# vcf-v1.net
KiCad netlist of a schematic drawn in EAGLE
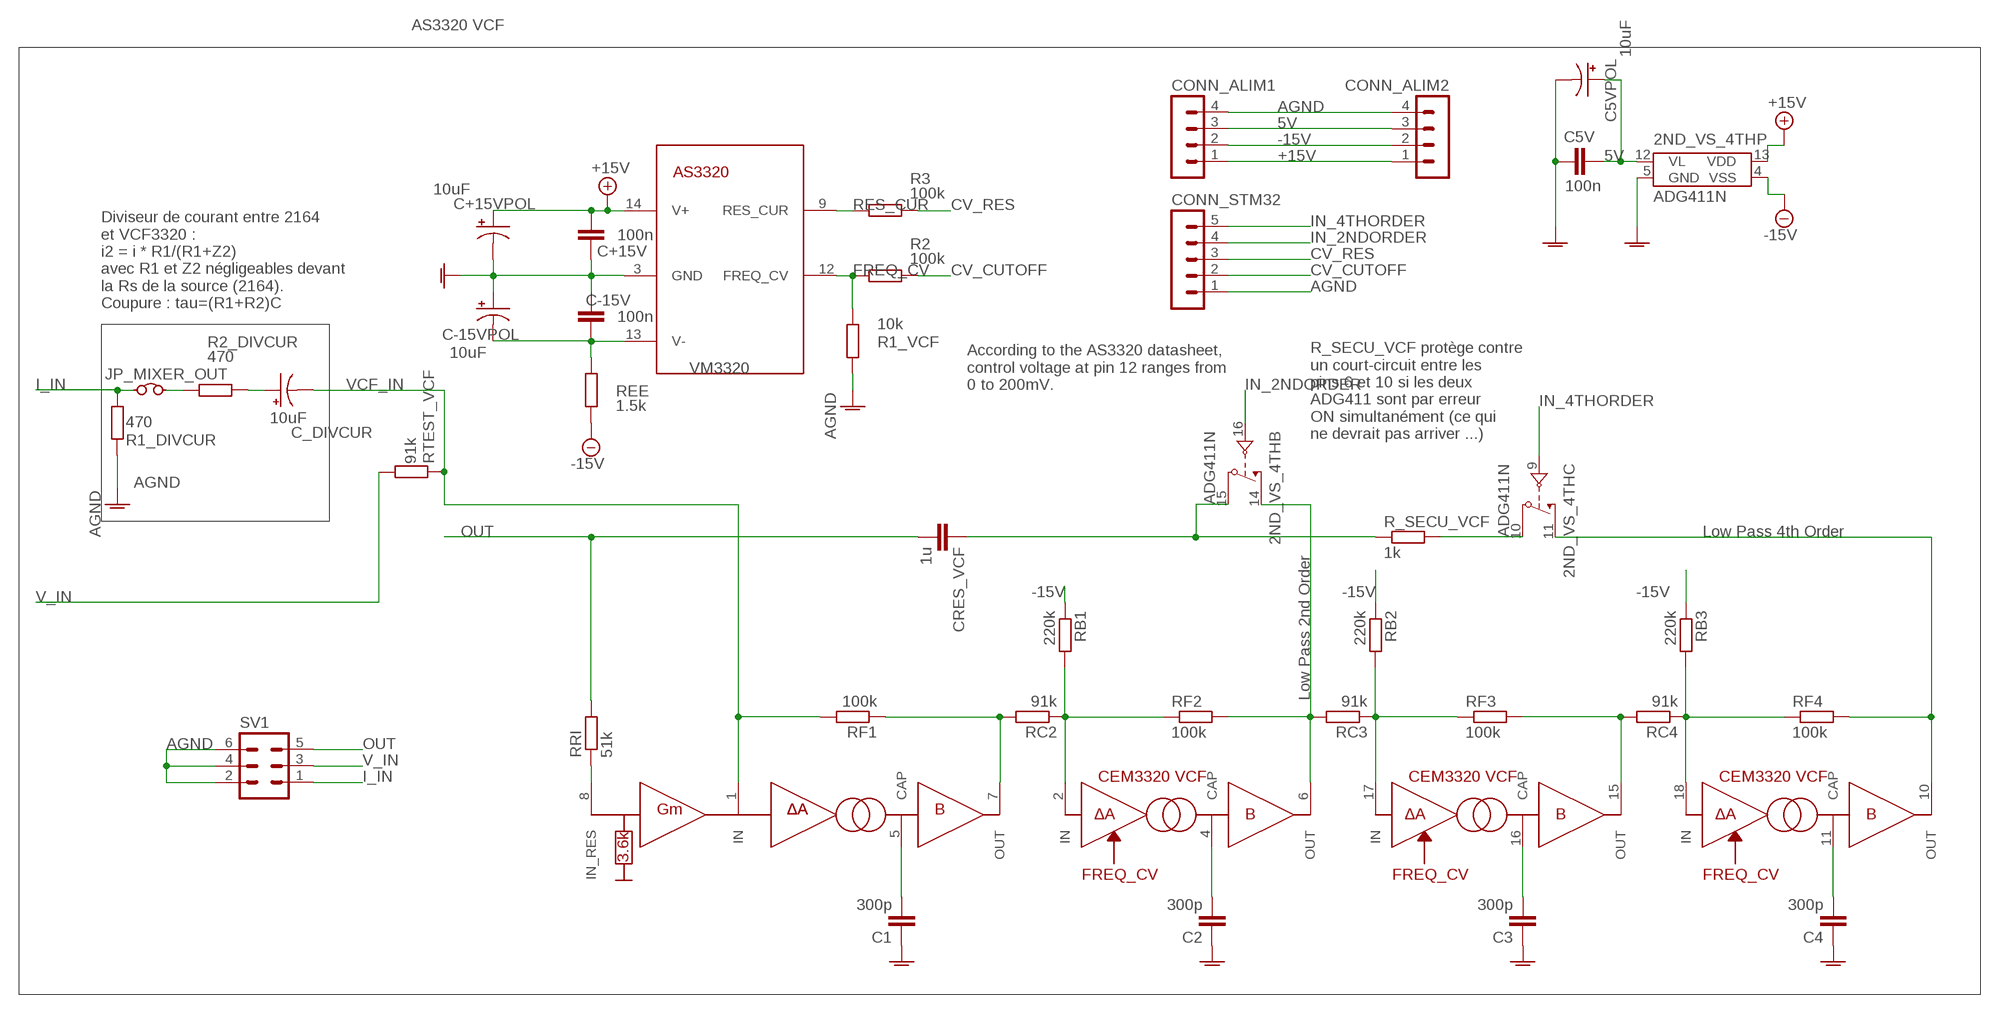
[diagram p0: schematic, sheet 1]

(export (version "E")
  (design (tool "Eeschema 10.0.6"))
  (components
    (comp (ref "2ND_VS_4TH")
      (value "ADG411N")
      (footprint "eagle-import:DIL16")
      (fields (field (name "MF") "ALTERA CORPORATION") (field (name "MPN") "ADG411BN"))
      (libsource (lib "eagle-import") (part "ADG411N"))
    )
    (comp (ref "C+15V")
      (value "100n")
      (footprint "eagle-import:C050-024X044")
      (libsource (lib "eagle-import") (part "C-EU050-024X044"))
    )
    (comp (ref "C+15VPOL")
      (value "10uF")
      (footprint "eagle-import:CPOL-RADIAL-2.5MM-5MM-KIT")
      (libsource (lib "eagle-import") (part "10UF-POLAR-RADIAL-2.5MM-KIT-25V-20%"))
    )
    (comp (ref "C-15V")
      (value "100n")
      (footprint "eagle-import:C050-024X044")
      (libsource (lib "eagle-import") (part "C-EU050-024X044"))
    )
    (comp (ref "C-15VPOL")
      (value "10uF")
      (footprint "eagle-import:CPOL-RADIAL-2.5MM-5MM-KIT")
      (libsource (lib "eagle-import") (part "10UF-POLAR-RADIAL-2.5MM-KIT-25V-20%"))
    )
    (comp (ref "C1")
      (value "300p")
      (footprint "eagle-import:C050-024X044")
      (libsource (lib "eagle-import") (part "C-EU050-024X044"))
    )
    (comp (ref "C2")
      (value "300p")
      (footprint "eagle-import:C050-024X044")
      (libsource (lib "eagle-import") (part "C-EU050-024X044"))
    )
    (comp (ref "C3")
      (value "300p")
      (footprint "eagle-import:C075-032X103")
      (libsource (lib "eagle-import") (part "C-EU075-032X103"))
    )
    (comp (ref "C4")
      (value "300p")
      (footprint "eagle-import:C050-024X044")
      (libsource (lib "eagle-import") (part "C-EU050-024X044"))
    )
    (comp (ref "C5V")
      (value "100n")
      (footprint "eagle-import:C050-024X044")
      (libsource (lib "eagle-import") (part "C-EU050-024X044"))
    )
    (comp (ref "C5VPOL")
      (value "10uF")
      (footprint "eagle-import:CPOL-RADIAL-2.5MM-5MM-KIT")
      (libsource (lib "eagle-import") (part "10UF-POLAR-RADIAL-2.5MM-KIT-25V-20%"))
    )
    (comp (ref "CONN_ALIM1")
      (value "MA04-1")
      (footprint "eagle-import:MA04-1")
      (libsource (lib "eagle-import") (part "MA04-1"))
    )
    (comp (ref "CONN_ALIM2")
      (value "MA04-1")
      (footprint "eagle-import:MA04-1")
      (libsource (lib "eagle-import") (part "MA04-1"))
    )
    (comp (ref "CONN_STM32")
      (value "MA05-1")
      (footprint "eagle-import:MA05-1")
      (libsource (lib "eagle-import") (part "MA05-1"))
    )
    (comp (ref "CRES_VCF")
      (value "1u")
      (footprint "eagle-import:C050-024X044")
      (libsource (lib "eagle-import") (part "C-EU050-024X044"))
    )
    (comp (ref "C_DIVCUR")
      (value "10uF")
      (footprint "eagle-import:CPOL-RADIAL-2.5MM-5MM-KIT")
      (libsource (lib "eagle-import") (part "10UF-POLAR-RADIAL-2.5MM-KIT-25V-20%"))
    )
    (comp (ref "JP_MIXER_OUT")
      (value "JUMPER_WIRE")
      (footprint "eagle-import:JUMPER")
      (libsource (lib "eagle-import") (part "JUMPER_WIRE"))
    )
    (comp (ref "R1_DIVCUR")
      (value "470")
      (footprint "eagle-import:0204_5")
      (libsource (lib "eagle-import") (part "R-EU_0204/5"))
    )
    (comp (ref "R1_VCF")
      (value "10k")
      (footprint "eagle-import:0204_5")
      (libsource (lib "eagle-import") (part "R-EU_0204/5"))
    )
    (comp (ref "R2")
      (value "100k")
      (footprint "eagle-import:0204_5")
      (libsource (lib "eagle-import") (part "R-EU_0204/5"))
    )
    (comp (ref "R2_DIVCUR")
      (value "470")
      (footprint "eagle-import:0204_5")
      (libsource (lib "eagle-import") (part "R-EU_0204/5"))
    )
    (comp (ref "R3")
      (value "100k")
      (footprint "eagle-import:0204_5")
      (libsource (lib "eagle-import") (part "R-EU_0204/5"))
    )
    (comp (ref "RB1")
      (value "220k")
      (footprint "eagle-import:0204_5")
      (libsource (lib "eagle-import") (part "R-EU_0204/5"))
    )
    (comp (ref "RB2")
      (value "220k")
      (footprint "eagle-import:0204_5")
      (libsource (lib "eagle-import") (part "R-EU_0204/5"))
    )
    (comp (ref "RB3")
      (value "220k")
      (footprint "eagle-import:0204_5")
      (libsource (lib "eagle-import") (part "R-EU_0204/5"))
    )
    (comp (ref "RC2")
      (value "91k")
      (footprint "eagle-import:0204_5")
      (libsource (lib "eagle-import") (part "R-EU_0204/5"))
    )
    (comp (ref "RC3")
      (value "91k")
      (footprint "eagle-import:0204_5")
      (libsource (lib "eagle-import") (part "R-EU_0204/5"))
    )
    (comp (ref "RC4")
      (value "91k")
      (footprint "eagle-import:0204_5")
      (libsource (lib "eagle-import") (part "R-EU_0204/5"))
    )
    (comp (ref "REE")
      (value "1.5k")
      (footprint "eagle-import:0204_5")
      (libsource (lib "eagle-import") (part "R-EU_0204/5"))
    )
    (comp (ref "RF1")
      (value "100k")
      (footprint "eagle-import:0204_5")
      (libsource (lib "eagle-import") (part "R-EU_0204/5"))
    )
    (comp (ref "RF2")
      (value "100k")
      (footprint "eagle-import:0204_5")
      (libsource (lib "eagle-import") (part "R-EU_0204/5"))
    )
    (comp (ref "RF3")
      (value "100k")
      (footprint "eagle-import:0204_5")
      (libsource (lib "eagle-import") (part "R-EU_0204/5"))
    )
    (comp (ref "RF4")
      (value "100k")
      (footprint "eagle-import:0204_5")
      (libsource (lib "eagle-import") (part "R-EU_0204/5"))
    )
    (comp (ref "RRI")
      (value "51k")
      (footprint "eagle-import:0204_5")
      (libsource (lib "eagle-import") (part "R-EU_0204/5"))
    )
    (comp (ref "RTEST_VCF")
      (value "91k")
      (footprint "eagle-import:0204_5")
      (libsource (lib "eagle-import") (part "R-EU_0204/5"))
    )
    (comp (ref "R_SECU_VCF")
      (value "1k")
      (footprint "eagle-import:0204_5")
      (libsource (lib "eagle-import") (part "R-EU_0204/5"))
    )
    (comp (ref "SV1")
      (value "MA03-2")
      (footprint "eagle-import:MA03-2")
      (libsource (lib "eagle-import") (part "MA03-2"))
    )
    (comp (ref "VCF")
      (value "AS3320")
      (footprint "eagle-import:DIL18")
      (libsource (lib "eagle-import") (part "AS3320"))
    )
  )
  (nets
    (net (code "1") (name "+15V") (class "Default")
      (node (ref "2ND_VS_4TH") (pin "13") (pinfunction "VDD_13") (pintype "power_in"))
      (node (ref "C+15V") (pin "2") (pinfunction "2_2") (pintype "passive"))
      (node (ref "C+15VPOL") (pin "1") (pinfunction "+_1") (pintype "passive"))
      (node (ref "CONN_ALIM1") (pin "1") (pinfunction "1_1") (pintype "passive"))
      (node (ref "CONN_ALIM2") (pin "1") (pinfunction "1_1") (pintype "passive"))
      (node (ref "VCF") (pin "14") (pinfunction "V+_14") (pintype "bidirectional"))
    )
    (net (code "2") (name "-15V") (class "Default")
      (node (ref "2ND_VS_4TH") (pin "4") (pinfunction "VSS_4") (pintype "power_in"))
      (node (ref "CONN_ALIM1") (pin "2") (pinfunction "2_2") (pintype "passive"))
      (node (ref "CONN_ALIM2") (pin "2") (pinfunction "2_2") (pintype "passive"))
      (node (ref "RB1") (pin "1") (pinfunction "1_1") (pintype "passive"))
      (node (ref "RB2") (pin "1") (pinfunction "1_1") (pintype "passive"))
      (node (ref "RB3") (pin "1") (pinfunction "1_1") (pintype "passive"))
      (node (ref "REE") (pin "1") (pinfunction "1_1") (pintype "passive"))
    )
    (net (code "3") (name "/5V") (class "Default")
      (node (ref "2ND_VS_4TH") (pin "12") (pinfunction "VL_12") (pintype "power_in"))
      (node (ref "C5V") (pin "1") (pinfunction "1_1") (pintype "passive"))
      (node (ref "C5VPOL") (pin "1") (pinfunction "+_1") (pintype "passive"))
      (node (ref "CONN_ALIM1") (pin "3") (pinfunction "3_3") (pintype "passive"))
      (node (ref "CONN_ALIM2") (pin "3") (pinfunction "3_3") (pintype "passive"))
    )
    (net (code "4") (name "/CV_CUTOFF") (class "Default")
      (node (ref "CONN_STM32") (pin "2") (pinfunction "2_2") (pintype "passive"))
      (node (ref "R2") (pin "2") (pinfunction "2_2") (pintype "passive"))
    )
    (net (code "5") (name "/CV_RES") (class "Default")
      (node (ref "CONN_STM32") (pin "3") (pinfunction "3_3") (pintype "passive"))
      (node (ref "R3") (pin "2") (pinfunction "2_2") (pintype "passive"))
    )
    (net (code "6") (name "/FREQ_CV") (class "Default")
      (node (ref "R1_VCF") (pin "1") (pinfunction "1_1") (pintype "passive"))
      (node (ref "R2") (pin "1") (pinfunction "1_1") (pintype "passive"))
      (node (ref "VCF") (pin "12") (pinfunction "FREQ_CV_12") (pintype "bidirectional"))
    )
    (net (code "7") (name "/IN_2NDORDER") (class "Default")
      (node (ref "2ND_VS_4TH") (pin "16") (pinfunction "IN_16") (pintype "input"))
      (node (ref "CONN_STM32") (pin "4") (pinfunction "4_4") (pintype "passive"))
    )
    (net (code "8") (name "/IN_4THORDER") (class "Default")
      (node (ref "2ND_VS_4TH") (pin "9") (pinfunction "IN_9") (pintype "input"))
      (node (ref "CONN_STM32") (pin "5") (pinfunction "5_5") (pintype "passive"))
    )
    (net (code "9") (name "/I_IN") (class "Default")
      (node (ref "JP_MIXER_OUT") (pin "1") (pinfunction "1_1") (pintype "passive"))
      (node (ref "R1_DIVCUR") (pin "1") (pinfunction "1_1") (pintype "passive"))
      (node (ref "SV1") (pin "1") (pinfunction "1_1") (pintype "passive"))
    )
    (net (code "10") (name "/OUT") (class "Default")
      (node (ref "CRES_VCF") (pin "2") (pinfunction "2_2") (pintype "passive"))
      (node (ref "RRI") (pin "2") (pinfunction "2_2") (pintype "passive"))
      (node (ref "SV1") (pin "5") (pinfunction "5_5") (pintype "passive"))
    )
    (net (code "11") (name "/RES_CUR") (class "Default")
      (node (ref "R3") (pin "1") (pinfunction "1_1") (pintype "passive"))
      (node (ref "VCF") (pin "9") (pinfunction "RES_CUR_9") (pintype "bidirectional"))
    )
    (net (code "12") (name "/VCF_IN") (class "Default")
      (node (ref "C_DIVCUR") (pin "2") (pinfunction "-_2") (pintype "passive"))
      (node (ref "RF1") (pin "2") (pinfunction "2_2") (pintype "passive"))
      (node (ref "RTEST_VCF") (pin "2") (pinfunction "2_2") (pintype "passive"))
      (node (ref "VCF") (pin "1") (pinfunction "IN_1") (pintype "bidirectional"))
    )
    (net (code "13") (name "/VM3320") (class "Default")
      (node (ref "C-15V") (pin "1") (pinfunction "1_1") (pintype "passive"))
      (node (ref "C-15VPOL") (pin "2") (pinfunction "-_2") (pintype "passive"))
      (node (ref "REE") (pin "2") (pinfunction "2_2") (pintype "passive"))
      (node (ref "VCF") (pin "13") (pinfunction "V-_13") (pintype "bidirectional"))
    )
    (net (code "14") (name "/V_IN") (class "Default")
      (node (ref "RTEST_VCF") (pin "1") (pinfunction "1_1") (pintype "passive"))
      (node (ref "SV1") (pin "3") (pinfunction "3_3") (pintype "passive"))
    )
    (net (code "15") (name "AGND") (class "Default")
      (node (ref "2ND_VS_4TH") (pin "5") (pinfunction "GND_5") (pintype "power_in"))
      (node (ref "C+15V") (pin "1") (pinfunction "1_1") (pintype "passive"))
      (node (ref "C+15VPOL") (pin "2") (pinfunction "-_2") (pintype "passive"))
      (node (ref "C-15V") (pin "2") (pinfunction "2_2") (pintype "passive"))
      (node (ref "C-15VPOL") (pin "1") (pinfunction "+_1") (pintype "passive"))
      (node (ref "C1") (pin "1") (pinfunction "1_1") (pintype "passive"))
      (node (ref "C2") (pin "1") (pinfunction "1_1") (pintype "passive"))
      (node (ref "C3") (pin "1") (pinfunction "1_1") (pintype "passive"))
      (node (ref "C4") (pin "1") (pinfunction "1_1") (pintype "passive"))
      (node (ref "C5V") (pin "2") (pinfunction "2_2") (pintype "passive"))
      (node (ref "C5VPOL") (pin "2") (pinfunction "-_2") (pintype "passive"))
      (node (ref "CONN_ALIM1") (pin "4") (pinfunction "4_4") (pintype "passive"))
      (node (ref "CONN_ALIM2") (pin "4") (pinfunction "4_4") (pintype "passive"))
      (node (ref "CONN_STM32") (pin "1") (pinfunction "1_1") (pintype "passive"))
      (node (ref "R1_DIVCUR") (pin "2") (pinfunction "2_2") (pintype "passive"))
      (node (ref "R1_VCF") (pin "2") (pinfunction "2_2") (pintype "passive"))
      (node (ref "SV1") (pin "2") (pinfunction "2_2") (pintype "passive"))
      (node (ref "SV1") (pin "4") (pinfunction "4_4") (pintype "passive"))
      (node (ref "SV1") (pin "6") (pinfunction "6_6") (pintype "passive"))
      (node (ref "VCF") (pin "3") (pinfunction "GND_3") (pintype "bidirectional"))
    )
    (net (code "16") (name "Net-(2ND_VS_4THB-D)") (class "Default")
      (node (ref "2ND_VS_4TH") (pin "15") (pinfunction "D_15") (pintype "passive"))
      (node (ref "CRES_VCF") (pin "1") (pinfunction "1_1") (pintype "passive"))
      (node (ref "R_SECU_VCF") (pin "1") (pinfunction "1_1") (pintype "passive"))
    )
    (net (code "17") (name "Net-(2ND_VS_4THB-S)") (class "Default")
      (node (ref "2ND_VS_4TH") (pin "14") (pinfunction "S_14") (pintype "passive"))
      (node (ref "RC3") (pin "2") (pinfunction "2_2") (pintype "passive"))
      (node (ref "RF2") (pin "2") (pinfunction "2_2") (pintype "passive"))
      (node (ref "VCF") (pin "6") (pinfunction "OUT_6") (pintype "bidirectional"))
    )
    (net (code "18") (name "Net-(2ND_VS_4THC-D)") (class "Default")
      (node (ref "2ND_VS_4TH") (pin "10") (pinfunction "D_10") (pintype "passive"))
      (node (ref "R_SECU_VCF") (pin "2") (pinfunction "2_2") (pintype "passive"))
    )
    (net (code "19") (name "Net-(2ND_VS_4THC-S)") (class "Default")
      (node (ref "2ND_VS_4TH") (pin "11") (pinfunction "S_11") (pintype "passive"))
      (node (ref "RF4") (pin "2") (pinfunction "2_2") (pintype "passive"))
      (node (ref "VCF") (pin "10") (pinfunction "OUT_10") (pintype "bidirectional"))
    )
    (net (code "20") (name "Net-(C_DIVCUR-+)") (class "Default")
      (node (ref "C_DIVCUR") (pin "1") (pinfunction "+_1") (pintype "passive"))
      (node (ref "R2_DIVCUR") (pin "1") (pinfunction "1_1") (pintype "passive"))
    )
    (net (code "21") (name "Net-(JP_MIXER_OUT-Pad2)") (class "Default")
      (node (ref "JP_MIXER_OUT") (pin "2") (pinfunction "2_2") (pintype "passive"))
      (node (ref "R2_DIVCUR") (pin "2") (pinfunction "2_2") (pintype "passive"))
    )
    (net (code "22") (name "Net-(VCFA-CAP)") (class "Default")
      (node (ref "C1") (pin "2") (pinfunction "2_2") (pintype "passive"))
      (node (ref "VCF") (pin "5") (pinfunction "CAP_5") (pintype "bidirectional"))
    )
    (net (code "23") (name "Net-(VCFA-IN_RES)") (class "Default")
      (node (ref "RRI") (pin "1") (pinfunction "1_1") (pintype "passive"))
      (node (ref "VCF") (pin "8") (pinfunction "IN_RES_8") (pintype "bidirectional"))
    )
    (net (code "24") (name "Net-(VCFA-OUT)") (class "Default")
      (node (ref "RC2") (pin "2") (pinfunction "2_2") (pintype "passive"))
      (node (ref "RF1") (pin "1") (pinfunction "1_1") (pintype "passive"))
      (node (ref "VCF") (pin "7") (pinfunction "OUT_7") (pintype "bidirectional"))
    )
    (net (code "25") (name "Net-(VCFB-CAP)") (class "Default")
      (node (ref "C2") (pin "2") (pinfunction "2_2") (pintype "passive"))
      (node (ref "VCF") (pin "4") (pinfunction "CAP_4") (pintype "bidirectional"))
    )
    (net (code "26") (name "Net-(VCFB-IN)") (class "Default")
      (node (ref "RB1") (pin "2") (pinfunction "2_2") (pintype "passive"))
      (node (ref "RC2") (pin "1") (pinfunction "1_1") (pintype "passive"))
      (node (ref "RF2") (pin "1") (pinfunction "1_1") (pintype "passive"))
      (node (ref "VCF") (pin "2") (pinfunction "IN_2") (pintype "bidirectional"))
    )
    (net (code "27") (name "Net-(VCFC-CAP)") (class "Default")
      (node (ref "C4") (pin "2") (pinfunction "2_2") (pintype "passive"))
      (node (ref "VCF") (pin "11") (pinfunction "CAP_11") (pintype "bidirectional"))
    )
    (net (code "28") (name "Net-(VCFC-IN)") (class "Default")
      (node (ref "RB3") (pin "2") (pinfunction "2_2") (pintype "passive"))
      (node (ref "RC4") (pin "1") (pinfunction "1_1") (pintype "passive"))
      (node (ref "RF4") (pin "1") (pinfunction "1_1") (pintype "passive"))
      (node (ref "VCF") (pin "18") (pinfunction "IN_18") (pintype "bidirectional"))
    )
    (net (code "29") (name "Net-(VCFD-CAP)") (class "Default")
      (node (ref "C3") (pin "2") (pinfunction "2_2") (pintype "passive"))
      (node (ref "VCF") (pin "16") (pinfunction "CAP_16") (pintype "bidirectional"))
    )
    (net (code "30") (name "Net-(VCFD-IN)") (class "Default")
      (node (ref "RB2") (pin "2") (pinfunction "2_2") (pintype "passive"))
      (node (ref "RC3") (pin "1") (pinfunction "1_1") (pintype "passive"))
      (node (ref "RF3") (pin "1") (pinfunction "1_1") (pintype "passive"))
      (node (ref "VCF") (pin "17") (pinfunction "IN_17") (pintype "bidirectional"))
    )
    (net (code "31") (name "Net-(VCFD-OUT)") (class "Default")
      (node (ref "RC4") (pin "2") (pinfunction "2_2") (pintype "passive"))
      (node (ref "RF3") (pin "2") (pinfunction "2_2") (pintype "passive"))
      (node (ref "VCF") (pin "15") (pinfunction "OUT_15") (pintype "bidirectional"))
    )
  )
)
